# DLY_LED_BOARD_20250710.net
KiCad netlist of a schematic drawn in Altium Designer
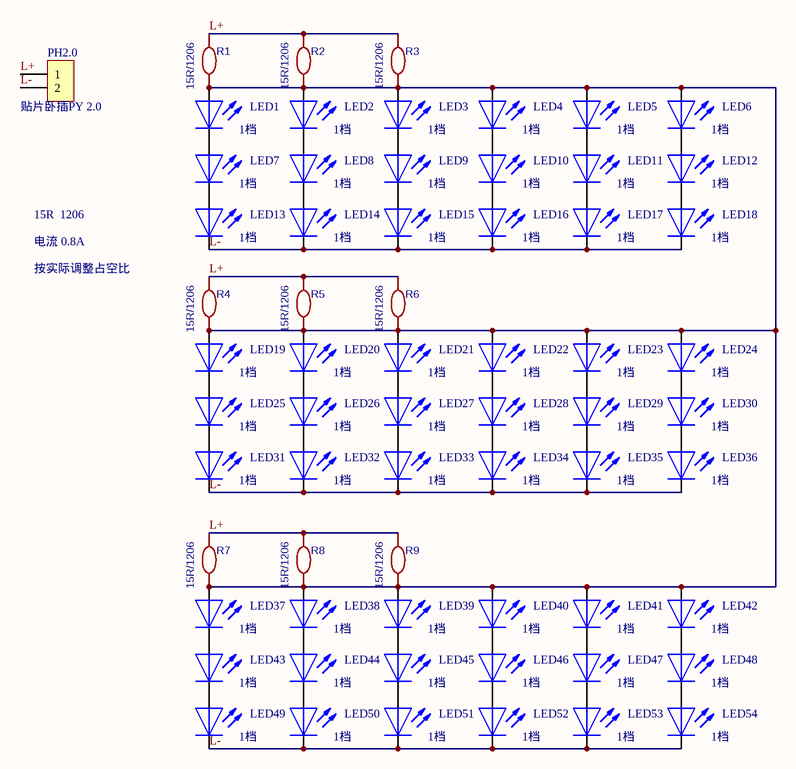
[diagram p0: DLY_LED_BOARD_20250710.SchDoc]

(export (version "E")
  (design (tool "Eeschema 10.0.6"))
  (components
    (comp (ref "LED1")
      (value "1档")
      (footprint "SMT-LED-2835")
      (libsource (lib "KENNED 原理图标准封装-20160624") (part "LED"))
    )
    (comp (ref "LED2")
      (value "1档")
      (footprint "SMT-LED-2835")
      (libsource (lib "KENNED 原理图标准封装-20160624") (part "LED"))
    )
    (comp (ref "LED3")
      (value "1档")
      (footprint "SMT-LED-2835")
      (libsource (lib "KENNED 原理图标准封装-20160624") (part "LED"))
    )
    (comp (ref "LED4")
      (value "1档")
      (footprint "SMT-LED-2835")
      (libsource (lib "KENNED 原理图标准封装-20160624") (part "LED"))
    )
    (comp (ref "LED5")
      (value "1档")
      (footprint "SMT-LED-2835")
      (libsource (lib "KENNED 原理图标准封装-20160624") (part "LED"))
    )
    (comp (ref "LED6")
      (value "1档")
      (footprint "SMT-LED-2835")
      (libsource (lib "KENNED 原理图标准封装-20160624") (part "LED"))
    )
    (comp (ref "LED7")
      (value "1档")
      (footprint "SMT-LED-2835")
      (libsource (lib "KENNED 原理图标准封装-20160624") (part "LED"))
    )
    (comp (ref "LED8")
      (value "1档")
      (footprint "SMT-LED-2835")
      (libsource (lib "KENNED 原理图标准封装-20160624") (part "LED"))
    )
    (comp (ref "LED9")
      (value "1档")
      (footprint "SMT-LED-2835")
      (libsource (lib "KENNED 原理图标准封装-20160624") (part "LED"))
    )
    (comp (ref "LED10")
      (value "1档")
      (footprint "SMT-LED-2835")
      (libsource (lib "KENNED 原理图标准封装-20160624") (part "LED"))
    )
    (comp (ref "LED11")
      (value "1档")
      (footprint "SMT-LED-2835")
      (libsource (lib "KENNED 原理图标准封装-20160624") (part "LED"))
    )
    (comp (ref "LED12")
      (value "1档")
      (footprint "SMT-LED-2835")
      (libsource (lib "KENNED 原理图标准封装-20160624") (part "LED"))
    )
    (comp (ref "LED13")
      (value "1档")
      (footprint "SMT-LED-2835")
      (libsource (lib "KENNED 原理图标准封装-20160624") (part "LED"))
    )
    (comp (ref "LED14")
      (value "1档")
      (footprint "SMT-LED-2835")
      (libsource (lib "KENNED 原理图标准封装-20160624") (part "LED"))
    )
    (comp (ref "LED15")
      (value "1档")
      (footprint "SMT-LED-2835")
      (libsource (lib "KENNED 原理图标准封装-20160624") (part "LED"))
    )
    (comp (ref "LED16")
      (value "1档")
      (footprint "SMT-LED-2835")
      (libsource (lib "KENNED 原理图标准封装-20160624") (part "LED"))
    )
    (comp (ref "LED17")
      (value "1档")
      (footprint "SMT-LED-2835")
      (libsource (lib "KENNED 原理图标准封装-20160624") (part "LED"))
    )
    (comp (ref "LED18")
      (value "1档")
      (footprint "SMT-LED-2835")
      (libsource (lib "KENNED 原理图标准封装-20160624") (part "LED"))
    )
    (comp (ref "LED19")
      (value "1档")
      (footprint "SMT-LED-2835")
      (libsource (lib "KENNED 原理图标准封装-20160624") (part "LED"))
    )
    (comp (ref "LED20")
      (value "1档")
      (footprint "SMT-LED-2835")
      (libsource (lib "KENNED 原理图标准封装-20160624") (part "LED"))
    )
    (comp (ref "LED21")
      (value "1档")
      (footprint "SMT-LED-2835")
      (libsource (lib "KENNED 原理图标准封装-20160624") (part "LED"))
    )
    (comp (ref "LED22")
      (value "1档")
      (footprint "SMT-LED-2835")
      (libsource (lib "KENNED 原理图标准封装-20160624") (part "LED"))
    )
    (comp (ref "LED23")
      (value "1档")
      (footprint "SMT-LED-2835")
      (libsource (lib "KENNED 原理图标准封装-20160624") (part "LED"))
    )
    (comp (ref "LED24")
      (value "1档")
      (footprint "SMT-LED-2835")
      (libsource (lib "KENNED 原理图标准封装-20160624") (part "LED"))
    )
    (comp (ref "LED25")
      (value "1档")
      (footprint "SMT-LED-2835")
      (libsource (lib "KENNED 原理图标准封装-20160624") (part "LED"))
    )
    (comp (ref "LED26")
      (value "1档")
      (footprint "SMT-LED-2835")
      (libsource (lib "KENNED 原理图标准封装-20160624") (part "LED"))
    )
    (comp (ref "LED27")
      (value "1档")
      (footprint "SMT-LED-2835")
      (libsource (lib "KENNED 原理图标准封装-20160624") (part "LED"))
    )
    (comp (ref "LED28")
      (value "1档")
      (footprint "SMT-LED-2835")
      (libsource (lib "KENNED 原理图标准封装-20160624") (part "LED"))
    )
    (comp (ref "LED29")
      (value "1档")
      (footprint "SMT-LED-2835")
      (libsource (lib "KENNED 原理图标准封装-20160624") (part "LED"))
    )
    (comp (ref "LED30")
      (value "1档")
      (footprint "SMT-LED-2835")
      (libsource (lib "KENNED 原理图标准封装-20160624") (part "LED"))
    )
    (comp (ref "LED31")
      (value "1档")
      (footprint "SMT-LED-2835")
      (libsource (lib "KENNED 原理图标准封装-20160624") (part "LED"))
    )
    (comp (ref "LED32")
      (value "1档")
      (footprint "SMT-LED-2835")
      (libsource (lib "KENNED 原理图标准封装-20160624") (part "LED"))
    )
    (comp (ref "LED33")
      (value "1档")
      (footprint "SMT-LED-2835")
      (libsource (lib "KENNED 原理图标准封装-20160624") (part "LED"))
    )
    (comp (ref "LED34")
      (value "1档")
      (footprint "SMT-LED-2835")
      (libsource (lib "KENNED 原理图标准封装-20160624") (part "LED"))
    )
    (comp (ref "LED35")
      (value "1档")
      (footprint "SMT-LED-2835")
      (libsource (lib "KENNED 原理图标准封装-20160624") (part "LED"))
    )
    (comp (ref "LED36")
      (value "1档")
      (footprint "SMT-LED-2835")
      (libsource (lib "KENNED 原理图标准封装-20160624") (part "LED"))
    )
    (comp (ref "LED37")
      (value "1档")
      (footprint "SMT-LED-2835")
      (libsource (lib "KENNED 原理图标准封装-20160624") (part "LED"))
    )
    (comp (ref "LED38")
      (value "1档")
      (footprint "SMT-LED-2835")
      (libsource (lib "KENNED 原理图标准封装-20160624") (part "LED"))
    )
    (comp (ref "LED39")
      (value "1档")
      (footprint "SMT-LED-2835")
      (libsource (lib "KENNED 原理图标准封装-20160624") (part "LED"))
    )
    (comp (ref "LED40")
      (value "1档")
      (footprint "SMT-LED-2835")
      (libsource (lib "KENNED 原理图标准封装-20160624") (part "LED"))
    )
    (comp (ref "LED41")
      (value "1档")
      (footprint "SMT-LED-2835")
      (libsource (lib "KENNED 原理图标准封装-20160624") (part "LED"))
    )
    (comp (ref "LED42")
      (value "1档")
      (footprint "SMT-LED-2835")
      (libsource (lib "KENNED 原理图标准封装-20160624") (part "LED"))
    )
    (comp (ref "LED43")
      (value "1档")
      (footprint "SMT-LED-2835")
      (libsource (lib "KENNED 原理图标准封装-20160624") (part "LED"))
    )
    (comp (ref "LED44")
      (value "1档")
      (footprint "SMT-LED-2835")
      (libsource (lib "KENNED 原理图标准封装-20160624") (part "LED"))
    )
    (comp (ref "LED45")
      (value "1档")
      (footprint "SMT-LED-2835")
      (libsource (lib "KENNED 原理图标准封装-20160624") (part "LED"))
    )
    (comp (ref "LED46")
      (value "1档")
      (footprint "SMT-LED-2835")
      (libsource (lib "KENNED 原理图标准封装-20160624") (part "LED"))
    )
    (comp (ref "LED47")
      (value "1档")
      (footprint "SMT-LED-2835")
      (libsource (lib "KENNED 原理图标准封装-20160624") (part "LED"))
    )
    (comp (ref "LED48")
      (value "1档")
      (footprint "SMT-LED-2835")
      (libsource (lib "KENNED 原理图标准封装-20160624") (part "LED"))
    )
    (comp (ref "LED49")
      (value "1档")
      (footprint "SMT-LED-2835")
      (libsource (lib "KENNED 原理图标准封装-20160624") (part "LED"))
    )
    (comp (ref "LED50")
      (value "1档")
      (footprint "SMT-LED-2835")
      (libsource (lib "KENNED 原理图标准封装-20160624") (part "LED"))
    )
    (comp (ref "LED51")
      (value "1档")
      (footprint "SMT-LED-2835")
      (libsource (lib "KENNED 原理图标准封装-20160624") (part "LED"))
    )
    (comp (ref "LED52")
      (value "1档")
      (footprint "SMT-LED-2835")
      (libsource (lib "KENNED 原理图标准封装-20160624") (part "LED"))
    )
    (comp (ref "LED53")
      (value "1档")
      (footprint "SMT-LED-2835")
      (libsource (lib "KENNED 原理图标准封装-20160624") (part "LED"))
    )
    (comp (ref "LED54")
      (value "1档")
      (footprint "SMT-LED-2835")
      (libsource (lib "KENNED 原理图标准封装-20160624") (part "LED"))
    )
    (comp (ref "PH2.0")
      (value "贴片卧插PY 2.0")
      (footprint "SMT-HY2.0-WT-2P")
      (libsource (lib "XH，VH") (part "XH2"))
    )
    (comp (ref "R1")
      (value "15R/1206")
      (footprint "SMT-1206R")
      (fields (field (name "CONTRIBUTOR") "LCEDA_Lib"))
      (libsource (lib "altium-import") (part "root_3_1k_"))
    )
    (comp (ref "R2")
      (value "15R/1206")
      (footprint "SMT-1206R")
      (fields (field (name "CONTRIBUTOR") "LCEDA_Lib"))
      (libsource (lib "altium-import") (part "root_3_1k_"))
    )
    (comp (ref "R3")
      (value "15R/1206")
      (footprint "SMT-1206R")
      (fields (field (name "CONTRIBUTOR") "LCEDA_Lib"))
      (libsource (lib "altium-import") (part "root_3_1k_"))
    )
    (comp (ref "R4")
      (value "15R/1206")
      (footprint "SMT-1206R")
      (fields (field (name "CONTRIBUTOR") "LCEDA_Lib"))
      (libsource (lib "altium-import") (part "root_3_1k_"))
    )
    (comp (ref "R5")
      (value "15R/1206")
      (footprint "SMT-1206R")
      (fields (field (name "CONTRIBUTOR") "LCEDA_Lib"))
      (libsource (lib "altium-import") (part "root_3_1k_"))
    )
    (comp (ref "R6")
      (value "15R/1206")
      (footprint "SMT-1206R")
      (fields (field (name "CONTRIBUTOR") "LCEDA_Lib"))
      (libsource (lib "altium-import") (part "root_3_1k_"))
    )
    (comp (ref "R7")
      (value "15R/1206")
      (footprint "SMT-1206R")
      (fields (field (name "CONTRIBUTOR") "LCEDA_Lib"))
      (libsource (lib "altium-import") (part "root_3_1k_"))
    )
    (comp (ref "R8")
      (value "15R/1206")
      (footprint "SMT-1206R")
      (fields (field (name "CONTRIBUTOR") "LCEDA_Lib"))
      (libsource (lib "altium-import") (part "root_3_1k_"))
    )
    (comp (ref "R9")
      (value "15R/1206")
      (footprint "SMT-1206R")
      (fields (field (name "CONTRIBUTOR") "LCEDA_Lib"))
      (libsource (lib "altium-import") (part "root_3_1k_"))
    )
  )
  (nets
    (net (code "1") (name "/L+") (class "Default")
      (node (ref "PH2.0") (pin "1") (pinfunction "1_1") (pintype "passive"))
      (node (ref "R1") (pin "1") (pinfunction "1_1") (pintype "passive"))
      (node (ref "R2") (pin "1") (pinfunction "1_1") (pintype "passive"))
      (node (ref "R3") (pin "1") (pinfunction "1_1") (pintype "passive"))
      (node (ref "R4") (pin "1") (pinfunction "1_1") (pintype "passive"))
      (node (ref "R5") (pin "1") (pinfunction "1_1") (pintype "passive"))
      (node (ref "R6") (pin "1") (pinfunction "1_1") (pintype "passive"))
      (node (ref "R7") (pin "1") (pinfunction "1_1") (pintype "passive"))
      (node (ref "R8") (pin "1") (pinfunction "1_1") (pintype "passive"))
      (node (ref "R9") (pin "1") (pinfunction "1_1") (pintype "passive"))
    )
    (net (code "2") (name "/L-") (class "Default")
      (node (ref "LED13") (pin "K") (pinfunction "2_K") (pintype "passive"))
      (node (ref "LED14") (pin "K") (pinfunction "2_K") (pintype "passive"))
      (node (ref "LED15") (pin "K") (pinfunction "2_K") (pintype "passive"))
      (node (ref "LED16") (pin "K") (pinfunction "2_K") (pintype "passive"))
      (node (ref "LED17") (pin "K") (pinfunction "2_K") (pintype "passive"))
      (node (ref "LED18") (pin "K") (pinfunction "2_K") (pintype "passive"))
      (node (ref "LED31") (pin "K") (pinfunction "2_K") (pintype "passive"))
      (node (ref "LED32") (pin "K") (pinfunction "2_K") (pintype "passive"))
      (node (ref "LED33") (pin "K") (pinfunction "2_K") (pintype "passive"))
      (node (ref "LED34") (pin "K") (pinfunction "2_K") (pintype "passive"))
      (node (ref "LED35") (pin "K") (pinfunction "2_K") (pintype "passive"))
      (node (ref "LED36") (pin "K") (pinfunction "2_K") (pintype "passive"))
      (node (ref "LED49") (pin "K") (pinfunction "2_K") (pintype "passive"))
      (node (ref "LED50") (pin "K") (pinfunction "2_K") (pintype "passive"))
      (node (ref "LED51") (pin "K") (pinfunction "2_K") (pintype "passive"))
      (node (ref "LED52") (pin "K") (pinfunction "2_K") (pintype "passive"))
      (node (ref "LED53") (pin "K") (pinfunction "2_K") (pintype "passive"))
      (node (ref "LED54") (pin "K") (pinfunction "2_K") (pintype "passive"))
      (node (ref "PH2.0") (pin "2") (pinfunction "2_2") (pintype "passive"))
    )
    (net (code "3") (name "Net-(LED1-1)") (class "Default")
      (node (ref "LED1") (pin "A") (pinfunction "1_A") (pintype "passive"))
      (node (ref "LED19") (pin "A") (pinfunction "1_A") (pintype "passive"))
      (node (ref "LED2") (pin "A") (pinfunction "1_A") (pintype "passive"))
      (node (ref "LED20") (pin "A") (pinfunction "1_A") (pintype "passive"))
      (node (ref "LED21") (pin "A") (pinfunction "1_A") (pintype "passive"))
      (node (ref "LED22") (pin "A") (pinfunction "1_A") (pintype "passive"))
      (node (ref "LED23") (pin "A") (pinfunction "1_A") (pintype "passive"))
      (node (ref "LED24") (pin "A") (pinfunction "1_A") (pintype "passive"))
      (node (ref "LED3") (pin "A") (pinfunction "1_A") (pintype "passive"))
      (node (ref "LED37") (pin "A") (pinfunction "1_A") (pintype "passive"))
      (node (ref "LED38") (pin "A") (pinfunction "1_A") (pintype "passive"))
      (node (ref "LED39") (pin "A") (pinfunction "1_A") (pintype "passive"))
      (node (ref "LED4") (pin "A") (pinfunction "1_A") (pintype "passive"))
      (node (ref "LED40") (pin "A") (pinfunction "1_A") (pintype "passive"))
      (node (ref "LED41") (pin "A") (pinfunction "1_A") (pintype "passive"))
      (node (ref "LED42") (pin "A") (pinfunction "1_A") (pintype "passive"))
      (node (ref "LED5") (pin "A") (pinfunction "1_A") (pintype "passive"))
      (node (ref "LED6") (pin "A") (pinfunction "1_A") (pintype "passive"))
      (node (ref "R1") (pin "2") (pinfunction "2_2") (pintype "passive"))
      (node (ref "R2") (pin "2") (pinfunction "2_2") (pintype "passive"))
      (node (ref "R3") (pin "2") (pinfunction "2_2") (pintype "passive"))
      (node (ref "R4") (pin "2") (pinfunction "2_2") (pintype "passive"))
      (node (ref "R5") (pin "2") (pinfunction "2_2") (pintype "passive"))
      (node (ref "R6") (pin "2") (pinfunction "2_2") (pintype "passive"))
      (node (ref "R7") (pin "2") (pinfunction "2_2") (pintype "passive"))
      (node (ref "R8") (pin "2") (pinfunction "2_2") (pintype "passive"))
      (node (ref "R9") (pin "2") (pinfunction "2_2") (pintype "passive"))
    )
    (net (code "4") (name "Net-(LED1-2)") (class "Default")
      (node (ref "LED1") (pin "K") (pinfunction "2_K") (pintype "passive"))
      (node (ref "LED7") (pin "A") (pinfunction "1_A") (pintype "passive"))
    )
    (net (code "5") (name "Net-(LED2-2)") (class "Default")
      (node (ref "LED2") (pin "K") (pinfunction "2_K") (pintype "passive"))
      (node (ref "LED8") (pin "A") (pinfunction "1_A") (pintype "passive"))
    )
    (net (code "6") (name "Net-(LED3-2)") (class "Default")
      (node (ref "LED3") (pin "K") (pinfunction "2_K") (pintype "passive"))
      (node (ref "LED9") (pin "A") (pinfunction "1_A") (pintype "passive"))
    )
    (net (code "7") (name "Net-(LED10-1)") (class "Default")
      (node (ref "LED10") (pin "A") (pinfunction "1_A") (pintype "passive"))
      (node (ref "LED4") (pin "K") (pinfunction "2_K") (pintype "passive"))
    )
    (net (code "8") (name "Net-(LED10-2)") (class "Default")
      (node (ref "LED10") (pin "K") (pinfunction "2_K") (pintype "passive"))
      (node (ref "LED16") (pin "A") (pinfunction "1_A") (pintype "passive"))
    )
    (net (code "9") (name "Net-(LED11-1)") (class "Default")
      (node (ref "LED11") (pin "A") (pinfunction "1_A") (pintype "passive"))
      (node (ref "LED5") (pin "K") (pinfunction "2_K") (pintype "passive"))
    )
    (net (code "10") (name "Net-(LED11-2)") (class "Default")
      (node (ref "LED11") (pin "K") (pinfunction "2_K") (pintype "passive"))
      (node (ref "LED17") (pin "A") (pinfunction "1_A") (pintype "passive"))
    )
    (net (code "11") (name "Net-(LED12-1)") (class "Default")
      (node (ref "LED12") (pin "A") (pinfunction "1_A") (pintype "passive"))
      (node (ref "LED6") (pin "K") (pinfunction "2_K") (pintype "passive"))
    )
    (net (code "12") (name "Net-(LED12-2)") (class "Default")
      (node (ref "LED12") (pin "K") (pinfunction "2_K") (pintype "passive"))
      (node (ref "LED18") (pin "A") (pinfunction "1_A") (pintype "passive"))
    )
    (net (code "13") (name "Net-(LED13-1)") (class "Default")
      (node (ref "LED13") (pin "A") (pinfunction "1_A") (pintype "passive"))
      (node (ref "LED7") (pin "K") (pinfunction "2_K") (pintype "passive"))
    )
    (net (code "14") (name "Net-(LED14-1)") (class "Default")
      (node (ref "LED14") (pin "A") (pinfunction "1_A") (pintype "passive"))
      (node (ref "LED8") (pin "K") (pinfunction "2_K") (pintype "passive"))
    )
    (net (code "15") (name "Net-(LED15-1)") (class "Default")
      (node (ref "LED15") (pin "A") (pinfunction "1_A") (pintype "passive"))
      (node (ref "LED9") (pin "K") (pinfunction "2_K") (pintype "passive"))
    )
    (net (code "16") (name "Net-(LED19-2)") (class "Default")
      (node (ref "LED19") (pin "K") (pinfunction "2_K") (pintype "passive"))
      (node (ref "LED25") (pin "A") (pinfunction "1_A") (pintype "passive"))
    )
    (net (code "17") (name "Net-(LED20-2)") (class "Default")
      (node (ref "LED20") (pin "K") (pinfunction "2_K") (pintype "passive"))
      (node (ref "LED26") (pin "A") (pinfunction "1_A") (pintype "passive"))
    )
    (net (code "18") (name "Net-(LED21-2)") (class "Default")
      (node (ref "LED21") (pin "K") (pinfunction "2_K") (pintype "passive"))
      (node (ref "LED27") (pin "A") (pinfunction "1_A") (pintype "passive"))
    )
    (net (code "19") (name "Net-(LED22-2)") (class "Default")
      (node (ref "LED22") (pin "K") (pinfunction "2_K") (pintype "passive"))
      (node (ref "LED28") (pin "A") (pinfunction "1_A") (pintype "passive"))
    )
    (net (code "20") (name "Net-(LED23-2)") (class "Default")
      (node (ref "LED23") (pin "K") (pinfunction "2_K") (pintype "passive"))
      (node (ref "LED29") (pin "A") (pinfunction "1_A") (pintype "passive"))
    )
    (net (code "21") (name "Net-(LED24-2)") (class "Default")
      (node (ref "LED24") (pin "K") (pinfunction "2_K") (pintype "passive"))
      (node (ref "LED30") (pin "A") (pinfunction "1_A") (pintype "passive"))
    )
    (net (code "22") (name "Net-(LED25-2)") (class "Default")
      (node (ref "LED25") (pin "K") (pinfunction "2_K") (pintype "passive"))
      (node (ref "LED31") (pin "A") (pinfunction "1_A") (pintype "passive"))
    )
    (net (code "23") (name "Net-(LED26-2)") (class "Default")
      (node (ref "LED26") (pin "K") (pinfunction "2_K") (pintype "passive"))
      (node (ref "LED32") (pin "A") (pinfunction "1_A") (pintype "passive"))
    )
    (net (code "24") (name "Net-(LED27-2)") (class "Default")
      (node (ref "LED27") (pin "K") (pinfunction "2_K") (pintype "passive"))
      (node (ref "LED33") (pin "A") (pinfunction "1_A") (pintype "passive"))
    )
    (net (code "25") (name "Net-(LED28-2)") (class "Default")
      (node (ref "LED28") (pin "K") (pinfunction "2_K") (pintype "passive"))
      (node (ref "LED34") (pin "A") (pinfunction "1_A") (pintype "passive"))
    )
    (net (code "26") (name "Net-(LED29-2)") (class "Default")
      (node (ref "LED29") (pin "K") (pinfunction "2_K") (pintype "passive"))
      (node (ref "LED35") (pin "A") (pinfunction "1_A") (pintype "passive"))
    )
    (net (code "27") (name "Net-(LED30-2)") (class "Default")
      (node (ref "LED30") (pin "K") (pinfunction "2_K") (pintype "passive"))
      (node (ref "LED36") (pin "A") (pinfunction "1_A") (pintype "passive"))
    )
    (net (code "28") (name "Net-(LED37-2)") (class "Default")
      (node (ref "LED37") (pin "K") (pinfunction "2_K") (pintype "passive"))
      (node (ref "LED43") (pin "A") (pinfunction "1_A") (pintype "passive"))
    )
    (net (code "29") (name "Net-(LED38-2)") (class "Default")
      (node (ref "LED38") (pin "K") (pinfunction "2_K") (pintype "passive"))
      (node (ref "LED44") (pin "A") (pinfunction "1_A") (pintype "passive"))
    )
    (net (code "30") (name "Net-(LED39-2)") (class "Default")
      (node (ref "LED39") (pin "K") (pinfunction "2_K") (pintype "passive"))
      (node (ref "LED45") (pin "A") (pinfunction "1_A") (pintype "passive"))
    )
    (net (code "31") (name "Net-(LED40-2)") (class "Default")
      (node (ref "LED40") (pin "K") (pinfunction "2_K") (pintype "passive"))
      (node (ref "LED46") (pin "A") (pinfunction "1_A") (pintype "passive"))
    )
    (net (code "32") (name "Net-(LED41-2)") (class "Default")
      (node (ref "LED41") (pin "K") (pinfunction "2_K") (pintype "passive"))
      (node (ref "LED47") (pin "A") (pinfunction "1_A") (pintype "passive"))
    )
    (net (code "33") (name "Net-(LED42-2)") (class "Default")
      (node (ref "LED42") (pin "K") (pinfunction "2_K") (pintype "passive"))
      (node (ref "LED48") (pin "A") (pinfunction "1_A") (pintype "passive"))
    )
    (net (code "34") (name "Net-(LED43-2)") (class "Default")
      (node (ref "LED43") (pin "K") (pinfunction "2_K") (pintype "passive"))
      (node (ref "LED49") (pin "A") (pinfunction "1_A") (pintype "passive"))
    )
    (net (code "35") (name "Net-(LED44-2)") (class "Default")
      (node (ref "LED44") (pin "K") (pinfunction "2_K") (pintype "passive"))
      (node (ref "LED50") (pin "A") (pinfunction "1_A") (pintype "passive"))
    )
    (net (code "36") (name "Net-(LED45-2)") (class "Default")
      (node (ref "LED45") (pin "K") (pinfunction "2_K") (pintype "passive"))
      (node (ref "LED51") (pin "A") (pinfunction "1_A") (pintype "passive"))
    )
    (net (code "37") (name "Net-(LED46-2)") (class "Default")
      (node (ref "LED46") (pin "K") (pinfunction "2_K") (pintype "passive"))
      (node (ref "LED52") (pin "A") (pinfunction "1_A") (pintype "passive"))
    )
    (net (code "38") (name "Net-(LED47-2)") (class "Default")
      (node (ref "LED47") (pin "K") (pinfunction "2_K") (pintype "passive"))
      (node (ref "LED53") (pin "A") (pinfunction "1_A") (pintype "passive"))
    )
    (net (code "39") (name "Net-(LED48-2)") (class "Default")
      (node (ref "LED48") (pin "K") (pinfunction "2_K") (pintype "passive"))
      (node (ref "LED54") (pin "A") (pinfunction "1_A") (pintype "passive"))
    )
  )
)
